# DVK2C-breakout.net
KiCad netlist of a schematic drawn in EAGLE
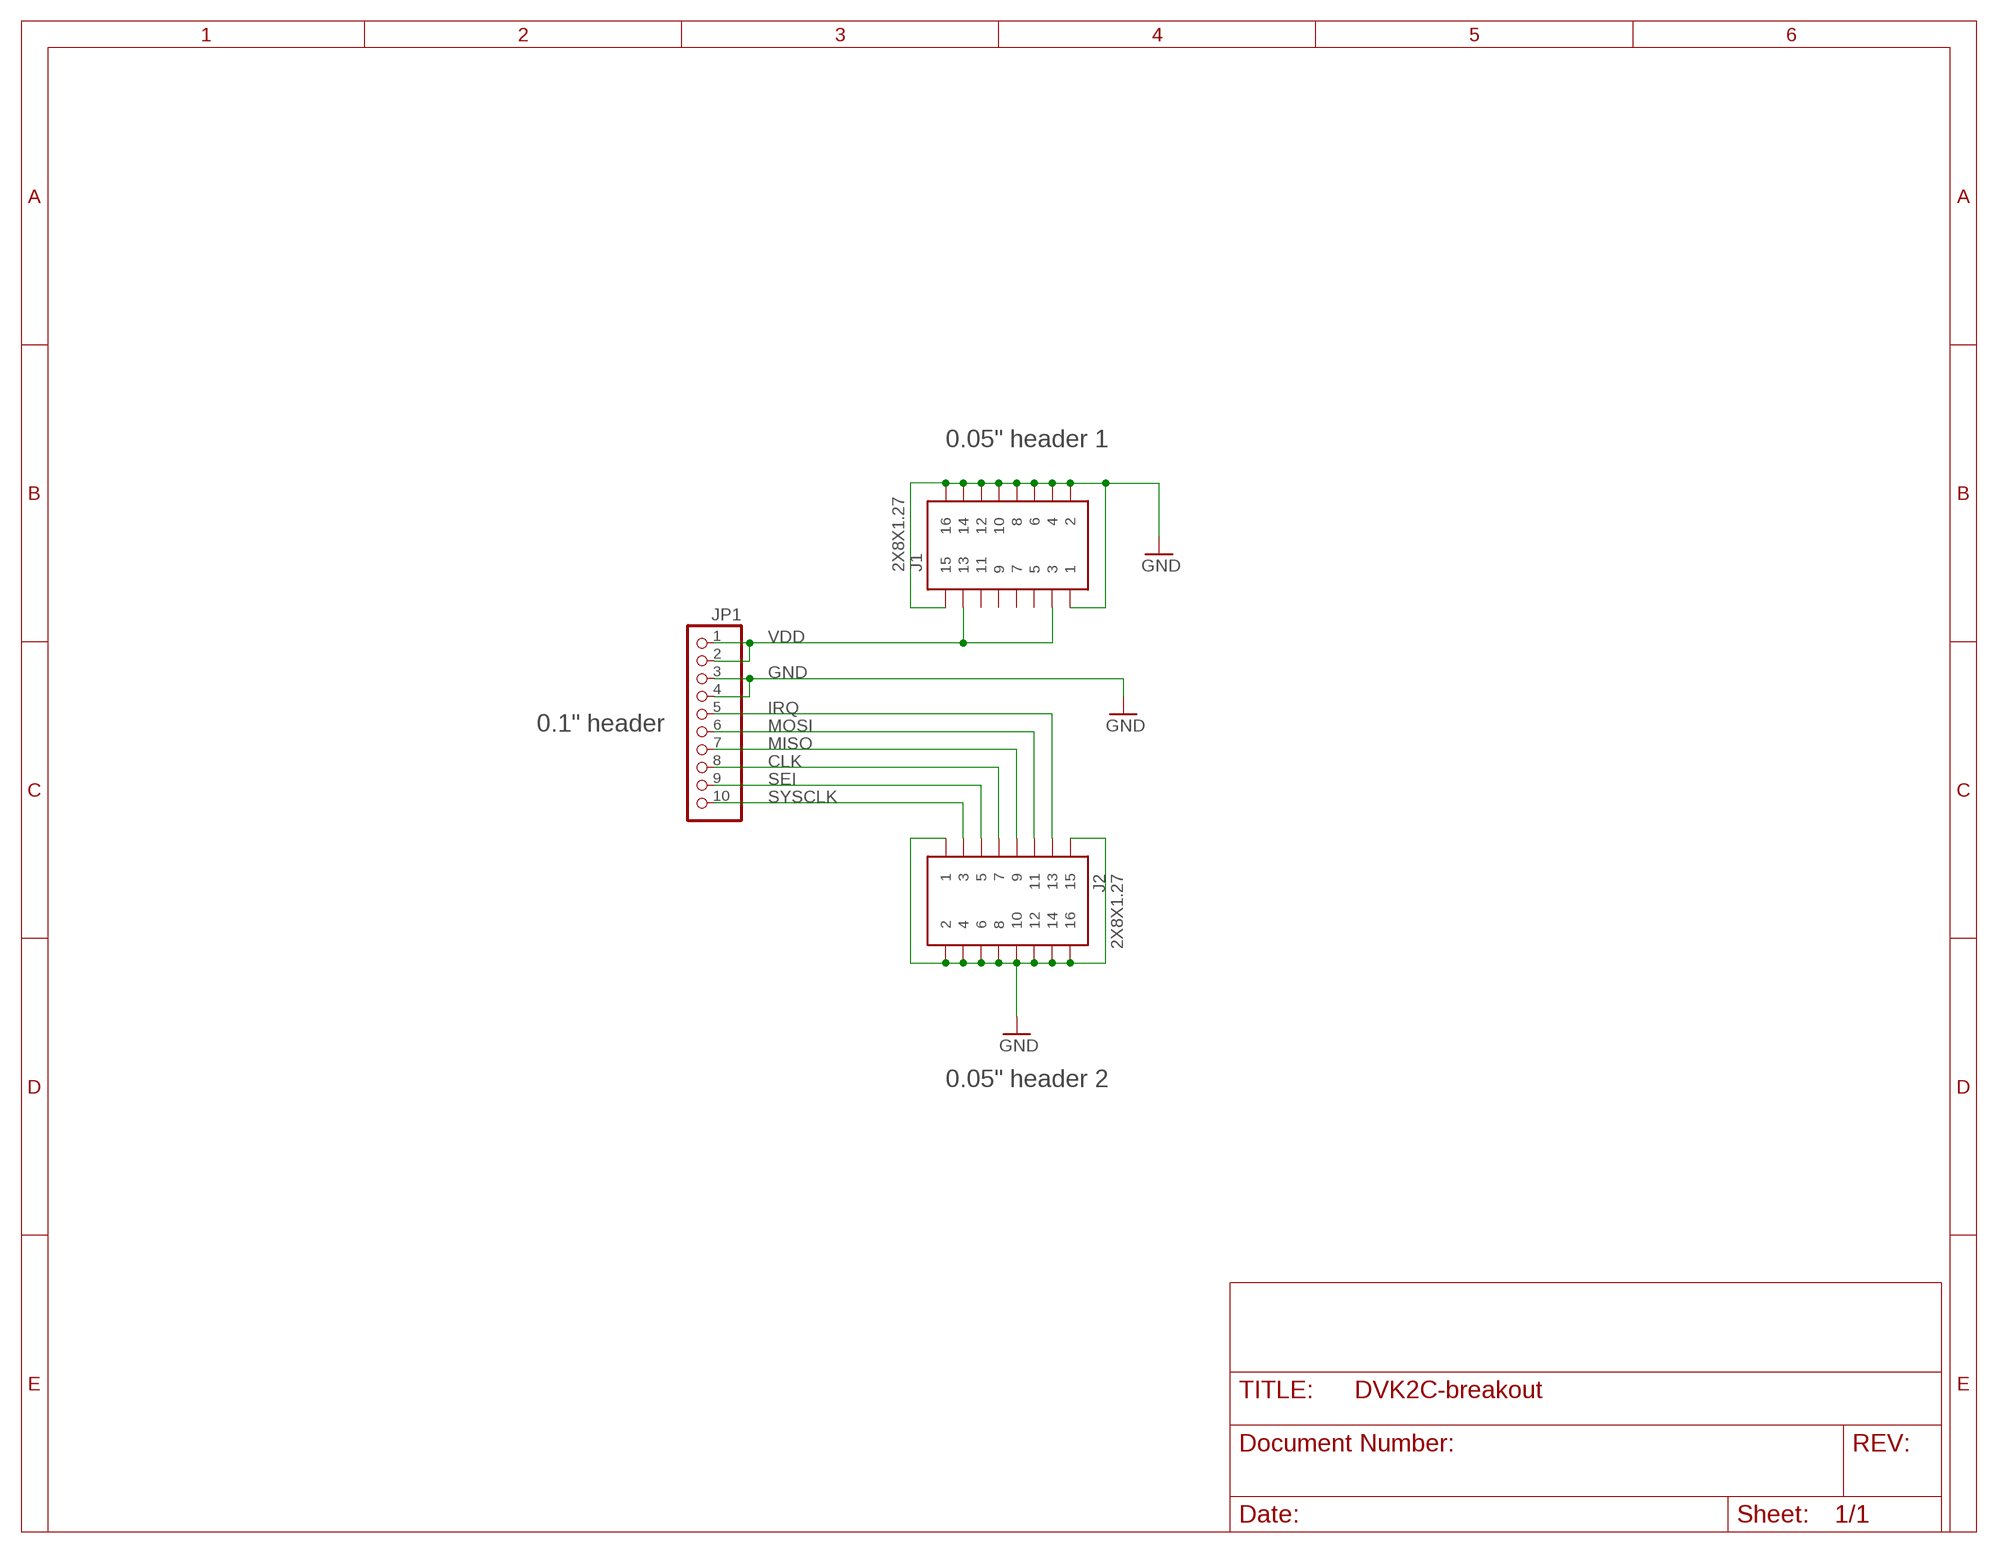
[diagram p0: schematic, sheet 1]

(export (version "E")
  (design (tool "Eeschema 10.0.6"))
  (components
    (comp (ref "J1")
      (value "2X8X1.27")
      (footprint "eagle-import:2X8X1.27")
      (libsource (lib "eagle-import") (part "2X8X1.27"))
    )
    (comp (ref "J2")
      (value "2X8X1.27")
      (footprint "eagle-import:2X8X1.27")
      (libsource (lib "eagle-import") (part "2X8X1.27"))
    )
    (comp (ref "JP1")
      (value "PINHD-1X10")
      (footprint "eagle-import:1X10")
      (libsource (lib "eagle-import") (part "PINHD-1X10"))
    )
  )
  (nets
    (net (code "1") (name "/CLK") (class "Default")
      (node (ref "J2") (pin "7") (pinfunction "7_7") (pintype "passive"))
      (node (ref "JP1") (pin "8") (pinfunction "8_8") (pintype "passive"))
    )
    (net (code "2") (name "/IRQ") (class "Default")
      (node (ref "J2") (pin "13") (pinfunction "13_13") (pintype "passive"))
      (node (ref "JP1") (pin "5") (pinfunction "5_5") (pintype "passive"))
    )
    (net (code "3") (name "/MISO") (class "Default")
      (node (ref "J2") (pin "9") (pinfunction "9_9") (pintype "passive"))
      (node (ref "JP1") (pin "7") (pinfunction "7_7") (pintype "passive"))
    )
    (net (code "4") (name "/MOSI") (class "Default")
      (node (ref "J2") (pin "11") (pinfunction "11_11") (pintype "passive"))
      (node (ref "JP1") (pin "6") (pinfunction "6_6") (pintype "passive"))
    )
    (net (code "5") (name "/SEI") (class "Default")
      (node (ref "J2") (pin "5") (pinfunction "5_5") (pintype "passive"))
      (node (ref "JP1") (pin "9") (pinfunction "9_9") (pintype "passive"))
    )
    (net (code "6") (name "/SYSCLK") (class "Default")
      (node (ref "J2") (pin "3") (pinfunction "3_3") (pintype "passive"))
      (node (ref "JP1") (pin "10") (pinfunction "10_10") (pintype "passive"))
    )
    (net (code "7") (name "/VDD") (class "Default")
      (node (ref "J1") (pin "13") (pinfunction "13_13") (pintype "passive"))
      (node (ref "J1") (pin "3") (pinfunction "3_3") (pintype "passive"))
      (node (ref "JP1") (pin "1") (pinfunction "1_1") (pintype "passive"))
      (node (ref "JP1") (pin "2") (pinfunction "2_2") (pintype "passive"))
    )
    (net (code "8") (name "GND") (class "Default")
      (node (ref "J1") (pin "1") (pinfunction "1_1") (pintype "passive"))
      (node (ref "J1") (pin "10") (pinfunction "10_10") (pintype "passive"))
      (node (ref "J1") (pin "12") (pinfunction "12_12") (pintype "passive"))
      (node (ref "J1") (pin "14") (pinfunction "14_14") (pintype "passive"))
      (node (ref "J1") (pin "15") (pinfunction "15_15") (pintype "passive"))
      (node (ref "J1") (pin "16") (pinfunction "16_16") (pintype "passive"))
      (node (ref "J1") (pin "2") (pinfunction "2_2") (pintype "passive"))
      (node (ref "J1") (pin "4") (pinfunction "4_4") (pintype "passive"))
      (node (ref "J1") (pin "6") (pinfunction "6_6") (pintype "passive"))
      (node (ref "J1") (pin "8") (pinfunction "8_8") (pintype "passive"))
      (node (ref "J2") (pin "1") (pinfunction "1_1") (pintype "passive"))
      (node (ref "J2") (pin "10") (pinfunction "10_10") (pintype "passive"))
      (node (ref "J2") (pin "12") (pinfunction "12_12") (pintype "passive"))
      (node (ref "J2") (pin "14") (pinfunction "14_14") (pintype "passive"))
      (node (ref "J2") (pin "15") (pinfunction "15_15") (pintype "passive"))
      (node (ref "J2") (pin "16") (pinfunction "16_16") (pintype "passive"))
      (node (ref "J2") (pin "2") (pinfunction "2_2") (pintype "passive"))
      (node (ref "J2") (pin "4") (pinfunction "4_4") (pintype "passive"))
      (node (ref "J2") (pin "6") (pinfunction "6_6") (pintype "passive"))
      (node (ref "J2") (pin "8") (pinfunction "8_8") (pintype "passive"))
      (node (ref "JP1") (pin "3") (pinfunction "3_3") (pintype "passive"))
      (node (ref "JP1") (pin "4") (pinfunction "4_4") (pintype "passive"))
    )
    (net (code "9") (name "unconnected-(J1-Pad5)") (class "Default")
      (node (ref "J1") (pin "5") (pinfunction "5_5") (pintype "passive"))
    )
    (net (code "10") (name "unconnected-(J1-Pad7)") (class "Default")
      (node (ref "J1") (pin "7") (pinfunction "7_7") (pintype "passive"))
    )
    (net (code "11") (name "unconnected-(J1-Pad9)") (class "Default")
      (node (ref "J1") (pin "9") (pinfunction "9_9") (pintype "passive"))
    )
    (net (code "12") (name "unconnected-(J1-Pad11)") (class "Default")
      (node (ref "J1") (pin "11") (pinfunction "11_11") (pintype "passive"))
    )
  )
)
